# Sheet1.net
KiCad netlist of a schematic drawn in Altium Designer
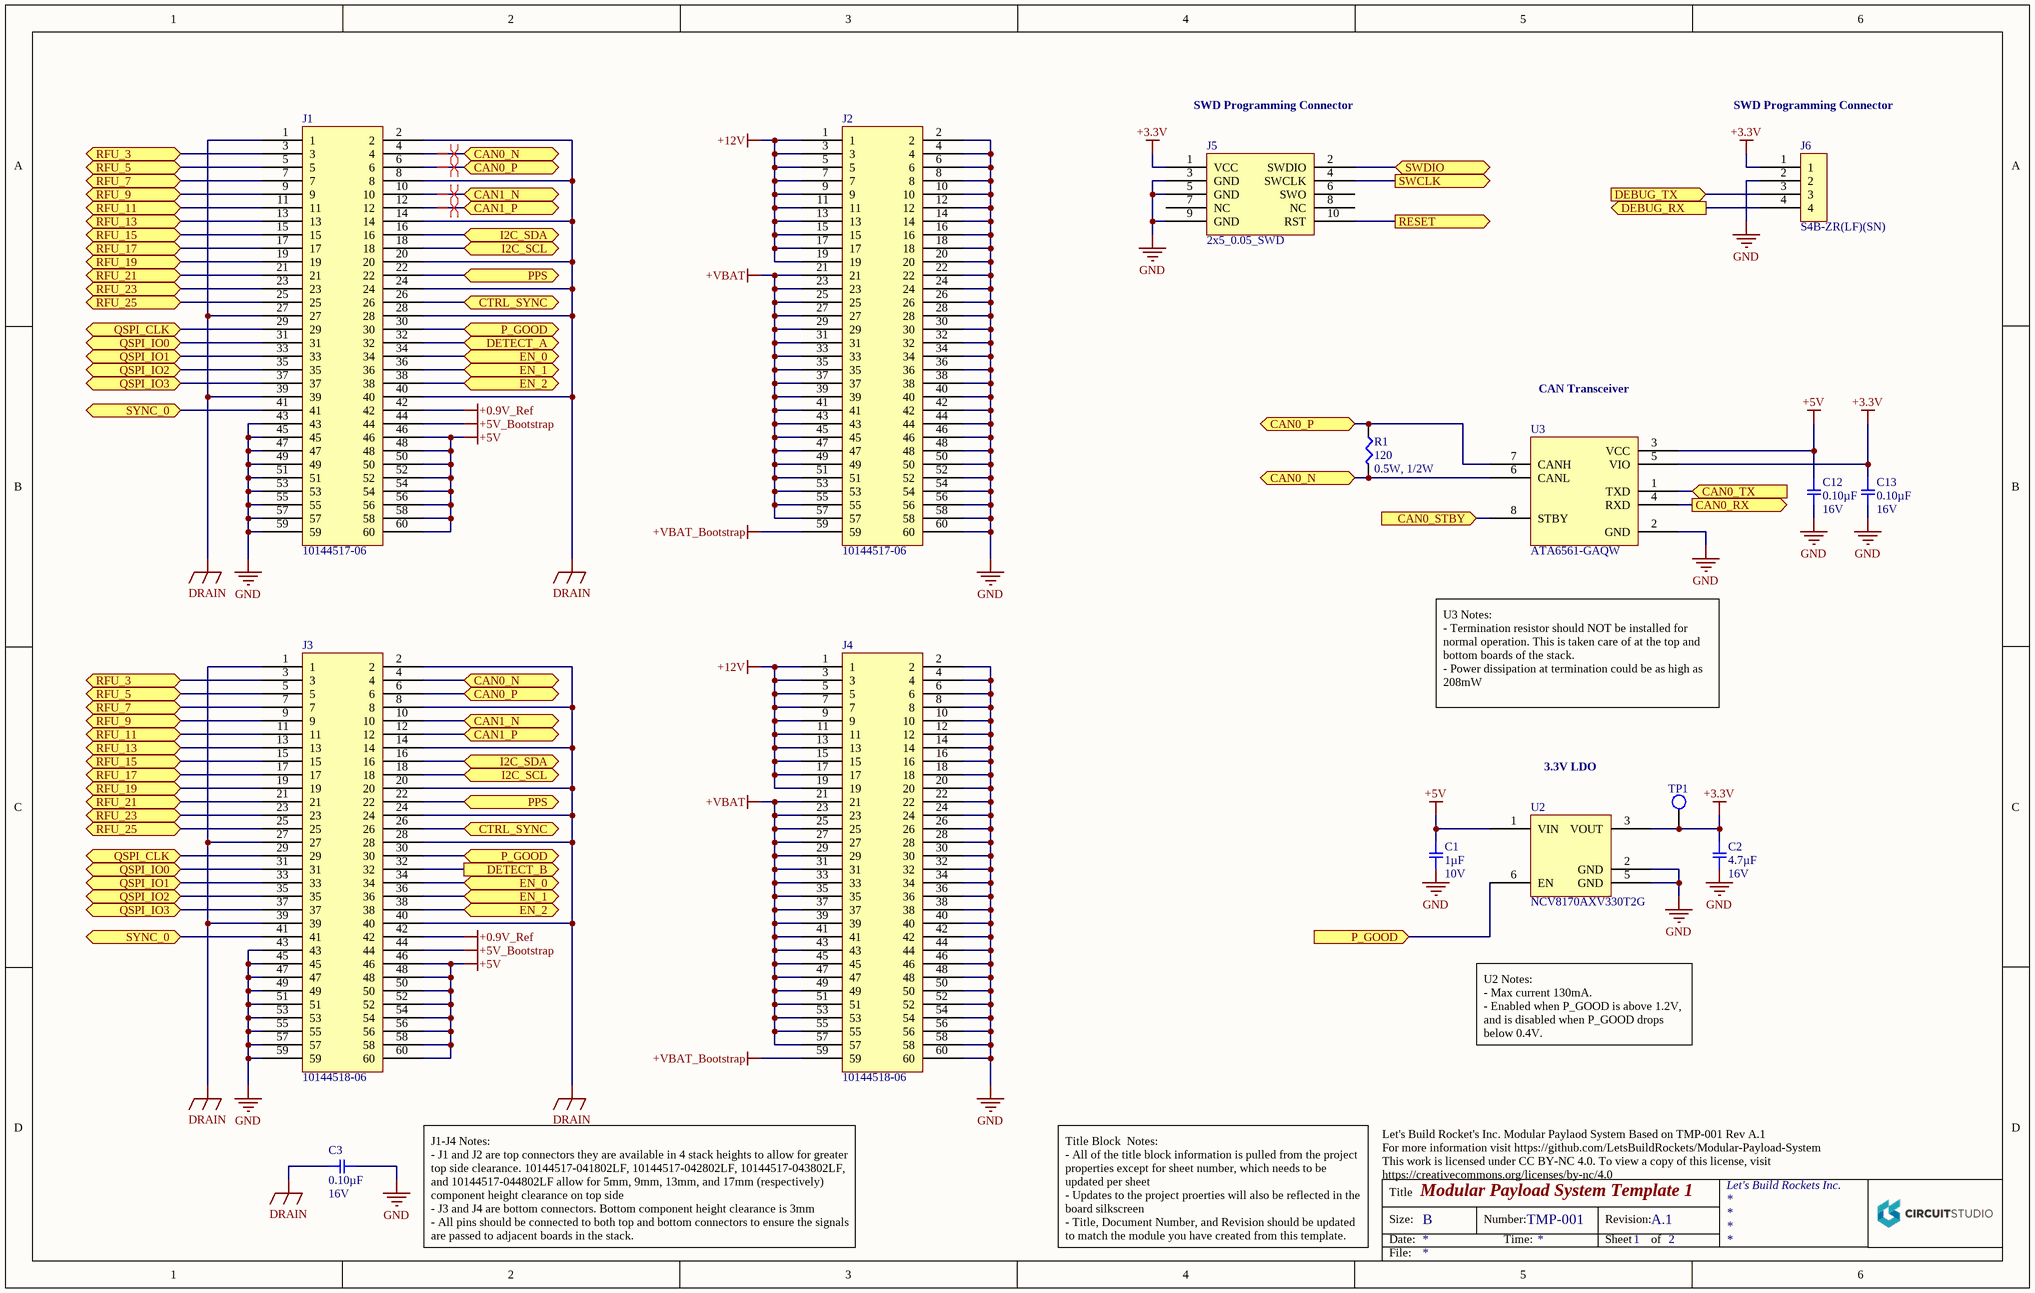
[diagram p0: Sheet1.SchDoc]

(export (version "E")
  (design (tool "Eeschema 10.0.6"))
  (components
    (comp (ref "C1")
      (value "1µF")
      (footprint "SMD-0402C")
      (description "CAP CER 1UF 10V X7S 0402")
      (fields
        (field (name "DIGI-KEY PART NUMBER") "490-13409-1-ND")
        (field (name "PART NUMBER") "GCM155C71A105KE38D")
        (field (name "VOLTAGE") "10V")
      )
      (libsource (lib "capacitor_murata_0402") (part "GCM155C71A105KE38D"))
    )
    (comp (ref "C2")
      (value "4.7µF")
      (footprint "SMD-0805C")
      (description "CAP CER 4.7UF 16V X7R 0805")
      (fields
        (field (name "DIGI-KEY PART NUMBER") "490-10557-1-ND")
        (field (name "PART NUMBER") "GCJ21BR71C475KA01L")
        (field (name "VOLTAGE") "16V")
      )
      (libsource (lib "capacitor_murata_0805") (part "GCJ21BR71C475KA01L"))
    )
    (comp (ref "C3")
      (value "0.10µF")
      (footprint "SMD-0402C")
      (description "CAP CER 0.1UF 16V X7R 0402")
      (fields
        (field (name "DIGI-KEY PART NUMBER") "490-4759-1-ND")
        (field (name "PART NUMBER") "GCM155R71C104KA55D")
        (field (name "VOLTAGE") "16V")
      )
      (libsource (lib "capacitor_murata_0402") (part "GCM155R71C104KA55D"))
    )
    (comp (ref "C12")
      (value "0.10µF")
      (footprint "SMD-0402C")
      (description "CAP CER 0.1UF 16V X7R 0402")
      (fields
        (field (name "DIGI-KEY PART NUMBER") "490-4759-1-ND")
        (field (name "PART NUMBER") "GCM155R71C104KA55D")
        (field (name "VOLTAGE") "16V")
      )
      (libsource (lib "capacitor_murata_0402") (part "GCM155R71C104KA55D"))
    )
    (comp (ref "C13")
      (value "0.10µF")
      (footprint "SMD-0402C")
      (description "CAP CER 0.1UF 16V X7R 0402")
      (fields
        (field (name "DIGI-KEY PART NUMBER") "490-4759-1-ND")
        (field (name "PART NUMBER") "GCM155R71C104KA55D")
        (field (name "VOLTAGE") "16V")
      )
      (libsource (lib "capacitor_murata_0402") (part "GCM155R71C104KA55D"))
    )
    (comp (ref "J1")
      (value "10144517-06")
      (footprint "10144517-062802LF")
      (libsource (lib "ModularPayload") (part "10144517-06"))
    )
    (comp (ref "J2")
      (value "10144517-06")
      (footprint "10144517-062802LF")
      (libsource (lib "ModularPayload") (part "10144517-06"))
    )
    (comp (ref "J3")
      (value "10144518-06")
      (footprint "10144518-064802LF")
      (libsource (lib "ModularPayload") (part "10144518-06"))
    )
    (comp (ref "J4")
      (value "10144518-06")
      (footprint "10144518-064802LF")
      (libsource (lib "ModularPayload") (part "10144518-06"))
    )
    (comp (ref "J5")
      (value "2x5_0.05_SWD")
      (footprint "2x5_0.05_R")
      (libsource (lib "ModularPayload") (part "2x5_0.05_SWD"))
    )
    (comp (ref "J6")
      (value "S4B-ZR(LF)(SN)")
      (footprint "S4B-ZR(LF)(SN)")
      (libsource (lib "ModularPayload") (part "S4B-ZR(LF)(SN)"))
    )
    (comp (ref "R1")
      (value "120")
      (footprint "SMD-0805-RES")
      (description "RES SMD 120 OHM 5% 1/2W 0805")
      (fields
        (field (name "PART NUMBER") "ERJ-P6WJ121V")
        (field (name "DIGI-KEY PART NUMBER") "P16943CT-ND")
        (field (name "POWER (WATTS)") "0.5W, 1/2W")
      )
      (libsource (lib "Panasonic_ERJ_0805") (part "ERJ-P6WJ121V"))
    )
    (comp (ref "TP1") (value "TP") (footprint "TP_SMD_40") (libsource (lib "TP") (part "TP")))
    (comp (ref "U2")
      (value "NCV8170AXV330T2G")
      (footprint "SOTFL50P160X60-6N")
      (libsource (lib "ModularPayload") (part "NCV8170AXV330T2G"))
    )
    (comp (ref "U3")
      (value "ATA6561-GAQW")
      (footprint "SOIC127P600X175-8N")
      (libsource (lib "ModularPayload") (part "ATA6561-GAQW"))
    )
  )
  (nets
    (net (code "1") (name "+0.9V_Ref") (class "Default")
      (node (ref "J1") (pin "42") (pinfunction "42_42") (pintype "passive"))
      (node (ref "J3") (pin "42") (pinfunction "42_42") (pintype "passive"))
    )
    (net (code "2") (name "+3.3V") (class "Default")
      (node (ref "C13") (pin "1") (pinfunction "1_1") (pintype "passive"))
      (node (ref "C2") (pin "2") (pinfunction "2_2") (pintype "passive"))
      (node (ref "J5") (pin "1") (pinfunction "VCC_1") (pintype "passive"))
      (node (ref "J6") (pin "1") (pinfunction "1_1") (pintype "passive"))
      (node (ref "TP1") (pin "1") (pintype "passive"))
      (node (ref "U2") (pin "3") (pinfunction "VOUT_3") (pintype "passive"))
      (node (ref "U3") (pin "5") (pinfunction "VIO_5") (pintype "passive"))
    )
    (net (code "3") (name "+5V") (class "Default")
      (node (ref "C1") (pin "2") (pinfunction "2_2") (pintype "passive"))
      (node (ref "C12") (pin "1") (pinfunction "1_1") (pintype "passive"))
      (node (ref "J1") (pin "46") (pinfunction "46_46") (pintype "passive"))
      (node (ref "J1") (pin "48") (pinfunction "48_48") (pintype "passive"))
      (node (ref "J1") (pin "50") (pinfunction "50_50") (pintype "passive"))
      (node (ref "J1") (pin "52") (pinfunction "52_52") (pintype "passive"))
      (node (ref "J1") (pin "54") (pinfunction "54_54") (pintype "passive"))
      (node (ref "J1") (pin "56") (pinfunction "56_56") (pintype "passive"))
      (node (ref "J1") (pin "58") (pinfunction "58_58") (pintype "passive"))
      (node (ref "J1") (pin "60") (pinfunction "60_60") (pintype "passive"))
      (node (ref "J3") (pin "46") (pinfunction "46_46") (pintype "passive"))
      (node (ref "J3") (pin "48") (pinfunction "48_48") (pintype "passive"))
      (node (ref "J3") (pin "50") (pinfunction "50_50") (pintype "passive"))
      (node (ref "J3") (pin "52") (pinfunction "52_52") (pintype "passive"))
      (node (ref "J3") (pin "54") (pinfunction "54_54") (pintype "passive"))
      (node (ref "J3") (pin "56") (pinfunction "56_56") (pintype "passive"))
      (node (ref "J3") (pin "58") (pinfunction "58_58") (pintype "passive"))
      (node (ref "J3") (pin "60") (pinfunction "60_60") (pintype "passive"))
      (node (ref "U2") (pin "1") (pinfunction "VIN_1") (pintype "passive"))
      (node (ref "U3") (pin "3") (pinfunction "VCC_3") (pintype "passive"))
    )
    (net (code "4") (name "+5V_Bootstrap") (class "Default")
      (node (ref "J1") (pin "44") (pinfunction "44_44") (pintype "passive"))
      (node (ref "J3") (pin "44") (pinfunction "44_44") (pintype "passive"))
    )
    (net (code "5") (name "+12V") (class "Default")
      (node (ref "J2") (pin "1") (pinfunction "1_1") (pintype "passive"))
      (node (ref "J2") (pin "11") (pinfunction "11_11") (pintype "passive"))
      (node (ref "J2") (pin "13") (pinfunction "13_13") (pintype "passive"))
      (node (ref "J2") (pin "15") (pinfunction "15_15") (pintype "passive"))
      (node (ref "J2") (pin "17") (pinfunction "17_17") (pintype "passive"))
      (node (ref "J2") (pin "19") (pinfunction "19_19") (pintype "passive"))
      (node (ref "J2") (pin "3") (pinfunction "3_3") (pintype "passive"))
      (node (ref "J2") (pin "5") (pinfunction "5_5") (pintype "passive"))
      (node (ref "J2") (pin "7") (pinfunction "7_7") (pintype "passive"))
      (node (ref "J2") (pin "9") (pinfunction "9_9") (pintype "passive"))
      (node (ref "J4") (pin "1") (pinfunction "1_1") (pintype "passive"))
      (node (ref "J4") (pin "11") (pinfunction "11_11") (pintype "passive"))
      (node (ref "J4") (pin "13") (pinfunction "13_13") (pintype "passive"))
      (node (ref "J4") (pin "15") (pinfunction "15_15") (pintype "passive"))
      (node (ref "J4") (pin "17") (pinfunction "17_17") (pintype "passive"))
      (node (ref "J4") (pin "19") (pinfunction "19_19") (pintype "passive"))
      (node (ref "J4") (pin "3") (pinfunction "3_3") (pintype "passive"))
      (node (ref "J4") (pin "5") (pinfunction "5_5") (pintype "passive"))
      (node (ref "J4") (pin "7") (pinfunction "7_7") (pintype "passive"))
      (node (ref "J4") (pin "9") (pinfunction "9_9") (pintype "passive"))
    )
    (net (code "6") (name "+VBAT") (class "Default")
      (node (ref "J2") (pin "21") (pinfunction "21_21") (pintype "passive"))
      (node (ref "J2") (pin "23") (pinfunction "23_23") (pintype "passive"))
      (node (ref "J2") (pin "25") (pinfunction "25_25") (pintype "passive"))
      (node (ref "J2") (pin "27") (pinfunction "27_27") (pintype "passive"))
      (node (ref "J2") (pin "29") (pinfunction "29_29") (pintype "passive"))
      (node (ref "J2") (pin "31") (pinfunction "31_31") (pintype "passive"))
      (node (ref "J2") (pin "33") (pinfunction "33_33") (pintype "passive"))
      (node (ref "J2") (pin "35") (pinfunction "35_35") (pintype "passive"))
      (node (ref "J2") (pin "37") (pinfunction "37_37") (pintype "passive"))
      (node (ref "J2") (pin "39") (pinfunction "39_39") (pintype "passive"))
      (node (ref "J2") (pin "41") (pinfunction "41_41") (pintype "passive"))
      (node (ref "J2") (pin "43") (pinfunction "43_43") (pintype "passive"))
      (node (ref "J2") (pin "45") (pinfunction "45_45") (pintype "passive"))
      (node (ref "J2") (pin "47") (pinfunction "47_47") (pintype "passive"))
      (node (ref "J2") (pin "49") (pinfunction "49_49") (pintype "passive"))
      (node (ref "J2") (pin "51") (pinfunction "51_51") (pintype "passive"))
      (node (ref "J2") (pin "53") (pinfunction "53_53") (pintype "passive"))
      (node (ref "J2") (pin "55") (pinfunction "55_55") (pintype "passive"))
      (node (ref "J2") (pin "57") (pinfunction "57_57") (pintype "passive"))
      (node (ref "J4") (pin "21") (pinfunction "21_21") (pintype "passive"))
      (node (ref "J4") (pin "23") (pinfunction "23_23") (pintype "passive"))
      (node (ref "J4") (pin "25") (pinfunction "25_25") (pintype "passive"))
      (node (ref "J4") (pin "27") (pinfunction "27_27") (pintype "passive"))
      (node (ref "J4") (pin "29") (pinfunction "29_29") (pintype "passive"))
      (node (ref "J4") (pin "31") (pinfunction "31_31") (pintype "passive"))
      (node (ref "J4") (pin "33") (pinfunction "33_33") (pintype "passive"))
      (node (ref "J4") (pin "35") (pinfunction "35_35") (pintype "passive"))
      (node (ref "J4") (pin "37") (pinfunction "37_37") (pintype "passive"))
      (node (ref "J4") (pin "39") (pinfunction "39_39") (pintype "passive"))
      (node (ref "J4") (pin "41") (pinfunction "41_41") (pintype "passive"))
      (node (ref "J4") (pin "43") (pinfunction "43_43") (pintype "passive"))
      (node (ref "J4") (pin "45") (pinfunction "45_45") (pintype "passive"))
      (node (ref "J4") (pin "47") (pinfunction "47_47") (pintype "passive"))
      (node (ref "J4") (pin "49") (pinfunction "49_49") (pintype "passive"))
      (node (ref "J4") (pin "51") (pinfunction "51_51") (pintype "passive"))
      (node (ref "J4") (pin "53") (pinfunction "53_53") (pintype "passive"))
      (node (ref "J4") (pin "55") (pinfunction "55_55") (pintype "passive"))
      (node (ref "J4") (pin "57") (pinfunction "57_57") (pintype "passive"))
    )
    (net (code "7") (name "+VBAT_Bootstrap") (class "Default")
      (node (ref "J2") (pin "59") (pinfunction "59_59") (pintype "passive"))
      (node (ref "J4") (pin "59") (pinfunction "59_59") (pintype "passive"))
    )
    (net (code "8") (name "/CAN0_N") (class "Default")
      (node (ref "J1") (pin "4") (pinfunction "4_4") (pintype "passive"))
      (node (ref "J3") (pin "4") (pinfunction "4_4") (pintype "passive"))
      (node (ref "R1") (pin "2") (pinfunction "2_2") (pintype "passive"))
      (node (ref "U3") (pin "6") (pinfunction "CANL_6") (pintype "passive"))
    )
    (net (code "9") (name "/CAN0_P") (class "Default")
      (node (ref "J1") (pin "6") (pinfunction "6_6") (pintype "passive"))
      (node (ref "J3") (pin "6") (pinfunction "6_6") (pintype "passive"))
      (node (ref "R1") (pin "1") (pinfunction "1_1") (pintype "passive"))
      (node (ref "U3") (pin "7") (pinfunction "CANH_7") (pintype "passive"))
    )
    (net (code "10") (name "/CAN0_RX") (class "Default")
      (node (ref "U3") (pin "4") (pinfunction "RXD_4") (pintype "passive"))
    )
    (net (code "11") (name "/CAN0_STBY") (class "Default")
      (node (ref "U3") (pin "8") (pinfunction "STBY_8") (pintype "passive"))
    )
    (net (code "12") (name "/CAN0_TX") (class "Default")
      (node (ref "U3") (pin "1") (pinfunction "TXD_1") (pintype "passive"))
    )
    (net (code "13") (name "/CAN1_N") (class "Default")
      (node (ref "J1") (pin "10") (pinfunction "10_10") (pintype "passive"))
      (node (ref "J3") (pin "10") (pinfunction "10_10") (pintype "passive"))
    )
    (net (code "14") (name "/CAN1_P") (class "Default")
      (node (ref "J1") (pin "12") (pinfunction "12_12") (pintype "passive"))
      (node (ref "J3") (pin "12") (pinfunction "12_12") (pintype "passive"))
    )
    (net (code "15") (name "/CTRL_SYNC") (class "Default")
      (node (ref "J1") (pin "26") (pinfunction "26_26") (pintype "passive"))
      (node (ref "J3") (pin "26") (pinfunction "26_26") (pintype "passive"))
    )
    (net (code "16") (name "/DEBUG_RX") (class "Default")
      (node (ref "J6") (pin "4") (pinfunction "4_4") (pintype "passive"))
    )
    (net (code "17") (name "/DEBUG_TX") (class "Default")
      (node (ref "J6") (pin "3") (pinfunction "3_3") (pintype "passive"))
    )
    (net (code "18") (name "/DETECT_A") (class "Default")
      (node (ref "J1") (pin "32") (pinfunction "32_32") (pintype "passive"))
    )
    (net (code "19") (name "/DETECT_B") (class "Default")
      (node (ref "J3") (pin "32") (pinfunction "32_32") (pintype "passive"))
    )
    (net (code "20") (name "/EN_0") (class "Default")
      (node (ref "J1") (pin "34") (pinfunction "34_34") (pintype "passive"))
      (node (ref "J3") (pin "34") (pinfunction "34_34") (pintype "passive"))
    )
    (net (code "21") (name "/EN_1") (class "Default")
      (node (ref "J1") (pin "36") (pinfunction "36_36") (pintype "passive"))
      (node (ref "J3") (pin "36") (pinfunction "36_36") (pintype "passive"))
    )
    (net (code "22") (name "/EN_2") (class "Default")
      (node (ref "J1") (pin "38") (pinfunction "38_38") (pintype "passive"))
      (node (ref "J3") (pin "38") (pinfunction "38_38") (pintype "passive"))
    )
    (net (code "23") (name "/I2C_SCL") (class "Default")
      (node (ref "J1") (pin "18") (pinfunction "18_18") (pintype "passive"))
      (node (ref "J3") (pin "18") (pinfunction "18_18") (pintype "passive"))
    )
    (net (code "24") (name "/I2C_SDA") (class "Default")
      (node (ref "J1") (pin "16") (pinfunction "16_16") (pintype "passive"))
      (node (ref "J3") (pin "16") (pinfunction "16_16") (pintype "passive"))
    )
    (net (code "25") (name "/PPS") (class "Default")
      (node (ref "J1") (pin "22") (pinfunction "22_22") (pintype "passive"))
      (node (ref "J3") (pin "22") (pinfunction "22_22") (pintype "passive"))
    )
    (net (code "26") (name "/P_GOOD") (class "Default")
      (node (ref "J1") (pin "30") (pinfunction "30_30") (pintype "passive"))
      (node (ref "J3") (pin "30") (pinfunction "30_30") (pintype "passive"))
      (node (ref "U2") (pin "6") (pinfunction "EN_6") (pintype "passive"))
    )
    (net (code "27") (name "/QSPI_CLK") (class "Default")
      (node (ref "J1") (pin "29") (pinfunction "29_29") (pintype "passive"))
      (node (ref "J3") (pin "29") (pinfunction "29_29") (pintype "passive"))
    )
    (net (code "28") (name "/QSPI_IO0") (class "Default")
      (node (ref "J1") (pin "31") (pinfunction "31_31") (pintype "passive"))
      (node (ref "J3") (pin "31") (pinfunction "31_31") (pintype "passive"))
    )
    (net (code "29") (name "/QSPI_IO1") (class "Default")
      (node (ref "J1") (pin "33") (pinfunction "33_33") (pintype "passive"))
      (node (ref "J3") (pin "33") (pinfunction "33_33") (pintype "passive"))
    )
    (net (code "30") (name "/QSPI_IO2") (class "Default")
      (node (ref "J1") (pin "35") (pinfunction "35_35") (pintype "passive"))
      (node (ref "J3") (pin "35") (pinfunction "35_35") (pintype "passive"))
    )
    (net (code "31") (name "/QSPI_IO3") (class "Default")
      (node (ref "J1") (pin "37") (pinfunction "37_37") (pintype "passive"))
      (node (ref "J3") (pin "37") (pinfunction "37_37") (pintype "passive"))
    )
    (net (code "32") (name "/RESET") (class "Default")
      (node (ref "J5") (pin "10") (pinfunction "RST_10") (pintype "passive"))
    )
    (net (code "33") (name "/RFU_3") (class "Default")
      (node (ref "J1") (pin "3") (pinfunction "3_3") (pintype "passive"))
      (node (ref "J3") (pin "3") (pinfunction "3_3") (pintype "passive"))
    )
    (net (code "34") (name "/RFU_5") (class "Default")
      (node (ref "J1") (pin "5") (pinfunction "5_5") (pintype "passive"))
      (node (ref "J3") (pin "5") (pinfunction "5_5") (pintype "passive"))
    )
    (net (code "35") (name "/RFU_7") (class "Default")
      (node (ref "J1") (pin "7") (pinfunction "7_7") (pintype "passive"))
      (node (ref "J3") (pin "7") (pinfunction "7_7") (pintype "passive"))
    )
    (net (code "36") (name "/RFU_9") (class "Default")
      (node (ref "J1") (pin "9") (pinfunction "9_9") (pintype "passive"))
      (node (ref "J3") (pin "9") (pinfunction "9_9") (pintype "passive"))
    )
    (net (code "37") (name "/RFU_11") (class "Default")
      (node (ref "J1") (pin "11") (pinfunction "11_11") (pintype "passive"))
      (node (ref "J3") (pin "11") (pinfunction "11_11") (pintype "passive"))
    )
    (net (code "38") (name "/RFU_13") (class "Default")
      (node (ref "J1") (pin "13") (pinfunction "13_13") (pintype "passive"))
      (node (ref "J3") (pin "13") (pinfunction "13_13") (pintype "passive"))
    )
    (net (code "39") (name "/RFU_15") (class "Default")
      (node (ref "J1") (pin "15") (pinfunction "15_15") (pintype "passive"))
      (node (ref "J3") (pin "15") (pinfunction "15_15") (pintype "passive"))
    )
    (net (code "40") (name "/RFU_17") (class "Default")
      (node (ref "J1") (pin "17") (pinfunction "17_17") (pintype "passive"))
      (node (ref "J3") (pin "17") (pinfunction "17_17") (pintype "passive"))
    )
    (net (code "41") (name "/RFU_19") (class "Default")
      (node (ref "J1") (pin "19") (pinfunction "19_19") (pintype "passive"))
      (node (ref "J3") (pin "19") (pinfunction "19_19") (pintype "passive"))
    )
    (net (code "42") (name "/RFU_21") (class "Default")
      (node (ref "J1") (pin "21") (pinfunction "21_21") (pintype "passive"))
      (node (ref "J3") (pin "21") (pinfunction "21_21") (pintype "passive"))
    )
    (net (code "43") (name "/RFU_23") (class "Default")
      (node (ref "J1") (pin "23") (pinfunction "23_23") (pintype "passive"))
      (node (ref "J3") (pin "23") (pinfunction "23_23") (pintype "passive"))
    )
    (net (code "44") (name "/RFU_25") (class "Default")
      (node (ref "J1") (pin "25") (pinfunction "25_25") (pintype "passive"))
      (node (ref "J3") (pin "25") (pinfunction "25_25") (pintype "passive"))
    )
    (net (code "45") (name "/SWCLK") (class "Default")
      (node (ref "J5") (pin "4") (pinfunction "SWCLK_4") (pintype "passive"))
    )
    (net (code "46") (name "/SWDIO") (class "Default")
      (node (ref "J5") (pin "2") (pinfunction "SWDIO_2") (pintype "passive"))
    )
    (net (code "47") (name "/SYNC_0") (class "Default")
      (node (ref "J1") (pin "41") (pinfunction "41_41") (pintype "passive"))
      (node (ref "J3") (pin "41") (pinfunction "41_41") (pintype "passive"))
    )
    (net (code "48") (name "DRAIN") (class "Default")
      (node (ref "C3") (pin "2") (pinfunction "2_2") (pintype "passive"))
      (node (ref "J1") (pin "1") (pinfunction "1_1") (pintype "passive"))
      (node (ref "J1") (pin "14") (pinfunction "14_14") (pintype "passive"))
      (node (ref "J1") (pin "2") (pinfunction "2_2") (pintype "passive"))
      (node (ref "J1") (pin "20") (pinfunction "20_20") (pintype "passive"))
      (node (ref "J1") (pin "24") (pinfunction "24_24") (pintype "passive"))
      (node (ref "J1") (pin "27") (pinfunction "27_27") (pintype "passive"))
      (node (ref "J1") (pin "28") (pinfunction "28_28") (pintype "passive"))
      (node (ref "J1") (pin "39") (pinfunction "39_39") (pintype "passive"))
      (node (ref "J1") (pin "40") (pinfunction "40_40") (pintype "passive"))
      (node (ref "J1") (pin "8") (pinfunction "8_8") (pintype "passive"))
      (node (ref "J3") (pin "1") (pinfunction "1_1") (pintype "passive"))
      (node (ref "J3") (pin "14") (pinfunction "14_14") (pintype "passive"))
      (node (ref "J3") (pin "2") (pinfunction "2_2") (pintype "passive"))
      (node (ref "J3") (pin "20") (pinfunction "20_20") (pintype "passive"))
      (node (ref "J3") (pin "24") (pinfunction "24_24") (pintype "passive"))
      (node (ref "J3") (pin "27") (pinfunction "27_27") (pintype "passive"))
      (node (ref "J3") (pin "28") (pinfunction "28_28") (pintype "passive"))
      (node (ref "J3") (pin "39") (pinfunction "39_39") (pintype "passive"))
      (node (ref "J3") (pin "40") (pinfunction "40_40") (pintype "passive"))
      (node (ref "J3") (pin "8") (pinfunction "8_8") (pintype "passive"))
    )
    (net (code "49") (name "GND") (class "Default")
      (node (ref "C1") (pin "1") (pinfunction "1_1") (pintype "passive"))
      (node (ref "C12") (pin "2") (pinfunction "2_2") (pintype "passive"))
      (node (ref "C13") (pin "2") (pinfunction "2_2") (pintype "passive"))
      (node (ref "C2") (pin "1") (pinfunction "1_1") (pintype "passive"))
      (node (ref "C3") (pin "1") (pinfunction "1_1") (pintype "passive"))
      (node (ref "J1") (pin "43") (pinfunction "43_43") (pintype "passive"))
      (node (ref "J1") (pin "45") (pinfunction "45_45") (pintype "passive"))
      (node (ref "J1") (pin "47") (pinfunction "47_47") (pintype "passive"))
      (node (ref "J1") (pin "49") (pinfunction "49_49") (pintype "passive"))
      (node (ref "J1") (pin "51") (pinfunction "51_51") (pintype "passive"))
      (node (ref "J1") (pin "53") (pinfunction "53_53") (pintype "passive"))
      (node (ref "J1") (pin "55") (pinfunction "55_55") (pintype "passive"))
      (node (ref "J1") (pin "57") (pinfunction "57_57") (pintype "passive"))
      (node (ref "J1") (pin "59") (pinfunction "59_59") (pintype "passive"))
      (node (ref "J2") (pin "10") (pinfunction "10_10") (pintype "passive"))
      (node (ref "J2") (pin "12") (pinfunction "12_12") (pintype "passive"))
      (node (ref "J2") (pin "14") (pinfunction "14_14") (pintype "passive"))
      (node (ref "J2") (pin "16") (pinfunction "16_16") (pintype "passive"))
      (node (ref "J2") (pin "18") (pinfunction "18_18") (pintype "passive"))
      (node (ref "J2") (pin "2") (pinfunction "2_2") (pintype "passive"))
      (node (ref "J2") (pin "20") (pinfunction "20_20") (pintype "passive"))
      (node (ref "J2") (pin "22") (pinfunction "22_22") (pintype "passive"))
      (node (ref "J2") (pin "24") (pinfunction "24_24") (pintype "passive"))
      (node (ref "J2") (pin "26") (pinfunction "26_26") (pintype "passive"))
      (node (ref "J2") (pin "28") (pinfunction "28_28") (pintype "passive"))
      (node (ref "J2") (pin "30") (pinfunction "30_30") (pintype "passive"))
      (node (ref "J2") (pin "32") (pinfunction "32_32") (pintype "passive"))
      (node (ref "J2") (pin "34") (pinfunction "34_34") (pintype "passive"))
      (node (ref "J2") (pin "36") (pinfunction "36_36") (pintype "passive"))
      (node (ref "J2") (pin "38") (pinfunction "38_38") (pintype "passive"))
      (node (ref "J2") (pin "4") (pinfunction "4_4") (pintype "passive"))
      (node (ref "J2") (pin "40") (pinfunction "40_40") (pintype "passive"))
      (node (ref "J2") (pin "42") (pinfunction "42_42") (pintype "passive"))
      (node (ref "J2") (pin "44") (pinfunction "44_44") (pintype "passive"))
      (node (ref "J2") (pin "46") (pinfunction "46_46") (pintype "passive"))
      (node (ref "J2") (pin "48") (pinfunction "48_48") (pintype "passive"))
      (node (ref "J2") (pin "50") (pinfunction "50_50") (pintype "passive"))
      (node (ref "J2") (pin "52") (pinfunction "52_52") (pintype "passive"))
      (node (ref "J2") (pin "54") (pinfunction "54_54") (pintype "passive"))
      (node (ref "J2") (pin "56") (pinfunction "56_56") (pintype "passive"))
      (node (ref "J2") (pin "58") (pinfunction "58_58") (pintype "passive"))
      (node (ref "J2") (pin "6") (pinfunction "6_6") (pintype "passive"))
      (node (ref "J2") (pin "60") (pinfunction "60_60") (pintype "passive"))
      (node (ref "J2") (pin "8") (pinfunction "8_8") (pintype "passive"))
      (node (ref "J3") (pin "43") (pinfunction "43_43") (pintype "passive"))
      (node (ref "J3") (pin "45") (pinfunction "45_45") (pintype "passive"))
      (node (ref "J3") (pin "47") (pinfunction "47_47") (pintype "passive"))
      (node (ref "J3") (pin "49") (pinfunction "49_49") (pintype "passive"))
      (node (ref "J3") (pin "51") (pinfunction "51_51") (pintype "passive"))
      (node (ref "J3") (pin "53") (pinfunction "53_53") (pintype "passive"))
      (node (ref "J3") (pin "55") (pinfunction "55_55") (pintype "passive"))
      (node (ref "J3") (pin "57") (pinfunction "57_57") (pintype "passive"))
      (node (ref "J3") (pin "59") (pinfunction "59_59") (pintype "passive"))
      (node (ref "J4") (pin "10") (pinfunction "10_10") (pintype "passive"))
      (node (ref "J4") (pin "12") (pinfunction "12_12") (pintype "passive"))
      (node (ref "J4") (pin "14") (pinfunction "14_14") (pintype "passive"))
      (node (ref "J4") (pin "16") (pinfunction "16_16") (pintype "passive"))
      (node (ref "J4") (pin "18") (pinfunction "18_18") (pintype "passive"))
      (node (ref "J4") (pin "2") (pinfunction "2_2") (pintype "passive"))
      (node (ref "J4") (pin "20") (pinfunction "20_20") (pintype "passive"))
      (node (ref "J4") (pin "22") (pinfunction "22_22") (pintype "passive"))
      (node (ref "J4") (pin "24") (pinfunction "24_24") (pintype "passive"))
      (node (ref "J4") (pin "26") (pinfunction "26_26") (pintype "passive"))
      (node (ref "J4") (pin "28") (pinfunction "28_28") (pintype "passive"))
      (node (ref "J4") (pin "30") (pinfunction "30_30") (pintype "passive"))
      (node (ref "J4") (pin "32") (pinfunction "32_32") (pintype "passive"))
      (node (ref "J4") (pin "34") (pinfunction "34_34") (pintype "passive"))
      (node (ref "J4") (pin "36") (pinfunction "36_36") (pintype "passive"))
      (node (ref "J4") (pin "38") (pinfunction "38_38") (pintype "passive"))
      (node (ref "J4") (pin "4") (pinfunction "4_4") (pintype "passive"))
      (node (ref "J4") (pin "40") (pinfunction "40_40") (pintype "passive"))
      (node (ref "J4") (pin "42") (pinfunction "42_42") (pintype "passive"))
      (node (ref "J4") (pin "44") (pinfunction "44_44") (pintype "passive"))
      (node (ref "J4") (pin "46") (pinfunction "46_46") (pintype "passive"))
      (node (ref "J4") (pin "48") (pinfunction "48_48") (pintype "passive"))
      (node (ref "J4") (pin "50") (pinfunction "50_50") (pintype "passive"))
      (node (ref "J4") (pin "52") (pinfunction "52_52") (pintype "passive"))
      (node (ref "J4") (pin "54") (pinfunction "54_54") (pintype "passive"))
      (node (ref "J4") (pin "56") (pinfunction "56_56") (pintype "passive"))
      (node (ref "J4") (pin "58") (pinfunction "58_58") (pintype "passive"))
      (node (ref "J4") (pin "6") (pinfunction "6_6") (pintype "passive"))
      (node (ref "J4") (pin "60") (pinfunction "60_60") (pintype "passive"))
      (node (ref "J4") (pin "8") (pinfunction "8_8") (pintype "passive"))
      (node (ref "J5") (pin "3") (pinfunction "GND_3") (pintype "passive"))
      (node (ref "J5") (pin "5") (pinfunction "GND_5") (pintype "passive"))
      (node (ref "J5") (pin "9") (pinfunction "GND_9") (pintype "passive"))
      (node (ref "J6") (pin "2") (pinfunction "2_2") (pintype "passive"))
      (node (ref "U2") (pin "2") (pinfunction "GND_2") (pintype "passive"))
      (node (ref "U2") (pin "5") (pinfunction "GND_5") (pintype "passive"))
      (node (ref "U3") (pin "2") (pinfunction "GND_2") (pintype "passive"))
    )
    (net (code "50") (name "unconnected-(J5-NC-Pad7)") (class "Default")
      (node (ref "J5") (pin "7") (pinfunction "NC_7") (pintype "passive"))
    )
    (net (code "51") (name "unconnected-(J5-NC-Pad8)") (class "Default")
      (node (ref "J5") (pin "8") (pinfunction "NC_8") (pintype "passive"))
    )
    (net (code "52") (name "unconnected-(J5-SWO-Pad6)") (class "Default")
      (node (ref "J5") (pin "6") (pinfunction "SWO_6") (pintype "passive"))
    )
  )
)
